# User_Interface.net
KiCad netlist of a schematic drawn in Altium Designer
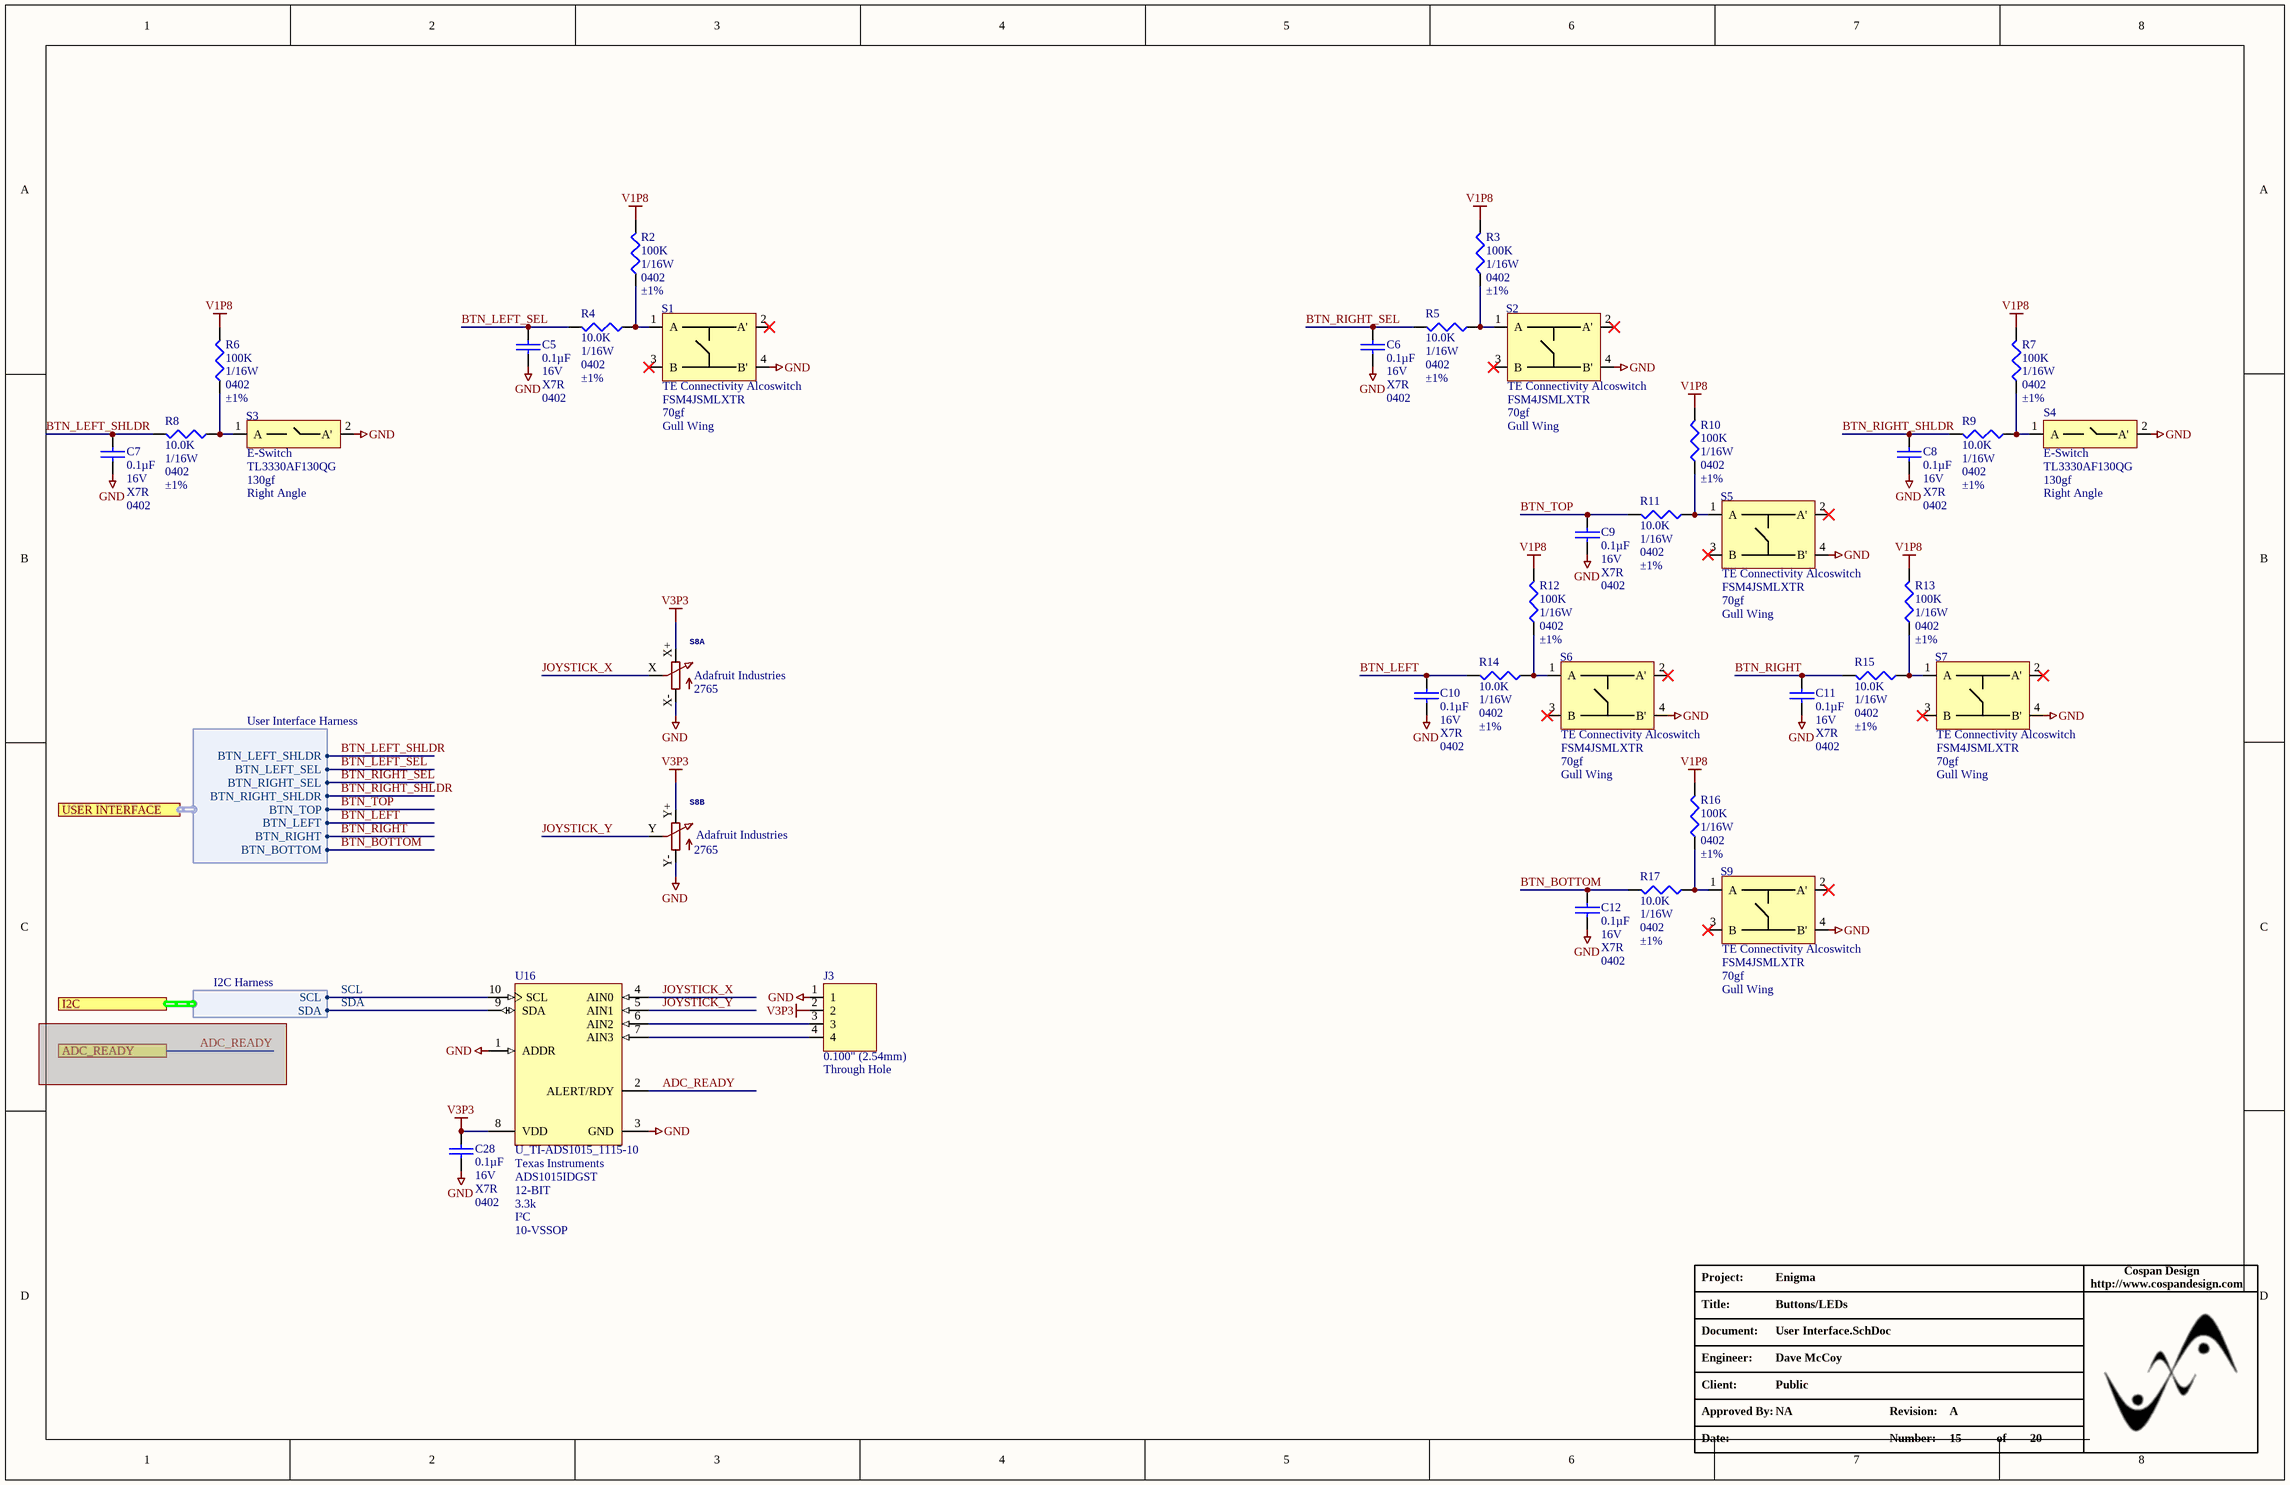
[diagram p0: User Interface.SchDoc]

(export (version "E")
  (design (tool "Eeschema 10.0.6"))
  (components
    (comp (ref "C5")
      (value "0.1uF")
      (footprint "C_0402")
      (description "CAP CER .10UF 16V X7R 0402")
      (fields
        (field (name "MANUFACTURER") "Murata Electronics North America")
        (field (name "MANUFACTURER PART NUMBER") "GRM155R71C104KA88J")
        (field (name "CAPACITANCE") "0.1µF")
        (field (name "VOLTAGE - RATED") "16V")
        (field (name "TEMPERATURE COEFFICIENT") "X7R")
        (field (name "PACKAGE / CASE") "0402")
      )
      (libsource (lib "Main LibraryX") (part "C_0402_0.1UF_16V"))
    )
    (comp (ref "C6")
      (value "0.1uF")
      (footprint "C_0402")
      (description "CAP CER .10UF 16V X7R 0402")
      (fields
        (field (name "MANUFACTURER") "Murata Electronics North America")
        (field (name "MANUFACTURER PART NUMBER") "GRM155R71C104KA88J")
        (field (name "CAPACITANCE") "0.1µF")
        (field (name "VOLTAGE - RATED") "16V")
        (field (name "TEMPERATURE COEFFICIENT") "X7R")
        (field (name "PACKAGE / CASE") "0402")
      )
      (libsource (lib "Main LibraryX") (part "C_0402_0.1UF_16V"))
    )
    (comp (ref "C7")
      (value "0.1uF")
      (footprint "C_0402")
      (description "CAP CER .10UF 16V X7R 0402")
      (fields
        (field (name "MANUFACTURER") "Murata Electronics North America")
        (field (name "MANUFACTURER PART NUMBER") "GRM155R71C104KA88J")
        (field (name "CAPACITANCE") "0.1µF")
        (field (name "VOLTAGE - RATED") "16V")
        (field (name "TEMPERATURE COEFFICIENT") "X7R")
        (field (name "PACKAGE / CASE") "0402")
      )
      (libsource (lib "Main LibraryX") (part "C_0402_0.1UF_16V"))
    )
    (comp (ref "C8")
      (value "0.1uF")
      (footprint "C_0402")
      (description "CAP CER .10UF 16V X7R 0402")
      (fields
        (field (name "MANUFACTURER") "Murata Electronics North America")
        (field (name "MANUFACTURER PART NUMBER") "GRM155R71C104KA88J")
        (field (name "CAPACITANCE") "0.1µF")
        (field (name "VOLTAGE - RATED") "16V")
        (field (name "TEMPERATURE COEFFICIENT") "X7R")
        (field (name "PACKAGE / CASE") "0402")
      )
      (libsource (lib "Main LibraryX") (part "C_0402_0.1UF_16V"))
    )
    (comp (ref "C9")
      (value "0.1uF")
      (footprint "C_0402")
      (description "CAP CER .10UF 16V X7R 0402")
      (fields
        (field (name "MANUFACTURER") "Murata Electronics North America")
        (field (name "MANUFACTURER PART NUMBER") "GRM155R71C104KA88J")
        (field (name "CAPACITANCE") "0.1µF")
        (field (name "VOLTAGE - RATED") "16V")
        (field (name "TEMPERATURE COEFFICIENT") "X7R")
        (field (name "PACKAGE / CASE") "0402")
      )
      (libsource (lib "Main LibraryX") (part "C_0402_0.1UF_16V"))
    )
    (comp (ref "C10")
      (value "0.1uF")
      (footprint "C_0402")
      (description "CAP CER .10UF 16V X7R 0402")
      (fields
        (field (name "MANUFACTURER") "Murata Electronics North America")
        (field (name "MANUFACTURER PART NUMBER") "GRM155R71C104KA88J")
        (field (name "CAPACITANCE") "0.1µF")
        (field (name "VOLTAGE - RATED") "16V")
        (field (name "TEMPERATURE COEFFICIENT") "X7R")
        (field (name "PACKAGE / CASE") "0402")
      )
      (libsource (lib "Main LibraryX") (part "C_0402_0.1UF_16V"))
    )
    (comp (ref "C11")
      (value "0.1uF")
      (footprint "C_0402")
      (description "CAP CER .10UF 16V X7R 0402")
      (fields
        (field (name "MANUFACTURER") "Murata Electronics North America")
        (field (name "MANUFACTURER PART NUMBER") "GRM155R71C104KA88J")
        (field (name "CAPACITANCE") "0.1µF")
        (field (name "VOLTAGE - RATED") "16V")
        (field (name "TEMPERATURE COEFFICIENT") "X7R")
        (field (name "PACKAGE / CASE") "0402")
      )
      (libsource (lib "Main LibraryX") (part "C_0402_0.1UF_16V"))
    )
    (comp (ref "C12")
      (value "0.1uF")
      (footprint "C_0402")
      (description "CAP CER .10UF 16V X7R 0402")
      (fields
        (field (name "MANUFACTURER") "Murata Electronics North America")
        (field (name "MANUFACTURER PART NUMBER") "GRM155R71C104KA88J")
        (field (name "CAPACITANCE") "0.1µF")
        (field (name "VOLTAGE - RATED") "16V")
        (field (name "TEMPERATURE COEFFICIENT") "X7R")
        (field (name "PACKAGE / CASE") "0402")
      )
      (libsource (lib "Main LibraryX") (part "C_0402_0.1UF_16V"))
    )
    (comp (ref "C28")
      (value "0.1uF")
      (footprint "C_0402")
      (description "CAP CER .10UF 16V X7R 0402")
      (fields
        (field (name "MANUFACTURER") "Murata Electronics North America")
        (field (name "MANUFACTURER PART NUMBER") "GRM155R71C104KA88J")
        (field (name "CAPACITANCE") "0.1µF")
        (field (name "VOLTAGE - RATED") "16V")
        (field (name "TEMPERATURE COEFFICIENT") "X7R")
        (field (name "PACKAGE / CASE") "0402")
      )
      (libsource (lib "Main LibraryX") (part "C_0402_0.1UF_16V"))
    )
    (comp (ref "J3")
      (value "J_HDR1X4_THRHOLE_VERT_FEMALE")
      (footprint "HDR_1X4_FEMALE")
      (description "CONN HEADER .100\" 4POS TIN PCB")
      (fields
        (field (name "MANUFACTURER") "Samtec Inc")
        (field (name "MANUFACTURER PART NUMBER") "SSW-116-01-T-S")
        (field (name "PITCH") "0.100\" (2.54mm)")
        (field (name "MOUNTING TYPE") "Through Hole")
      )
      (libsource (lib "Main Library") (part "J_HDR1X4_THRHOLE_VERT_FEMALE"))
    )
    (comp (ref "R2")
      (value "R_0402_100K")
      (footprint "R_0402")
      (description "RES SMD 100K OHM 1% 1/16W 0402")
      (fields
        (field (name "MANUFACTURER") "Yageo")
        (field (name "MANUFACTURER PART NUMBER") "RC0402FR-07100KL")
        (field (name "RESISTANCE IN OHMS") "100K")
        (field (name "POWER (WATTS)") "1/16W")
        (field (name "CASE") "0402")
        (field (name "TOLERANCE") "±1%")
      )
      (libsource (lib "Cospan Design") (part "R_0402_100K"))
    )
    (comp (ref "R3")
      (value "R_0402_100K")
      (footprint "R_0402")
      (description "RES SMD 100K OHM 1% 1/16W 0402")
      (fields
        (field (name "MANUFACTURER") "Yageo")
        (field (name "MANUFACTURER PART NUMBER") "RC0402FR-07100KL")
        (field (name "RESISTANCE IN OHMS") "100K")
        (field (name "POWER (WATTS)") "1/16W")
        (field (name "CASE") "0402")
        (field (name "TOLERANCE") "±1%")
      )
      (libsource (lib "Cospan Design") (part "R_0402_100K"))
    )
    (comp (ref "R4")
      (value "R_0402_10.0K")
      (footprint "R_0402")
      (description "RES 10.0K OHM 1/16W 1% 0402 SMD")
      (fields
        (field (name "MANUFACTURER") "Stackpole Electronics Inc")
        (field (name "MANUFACTURER PART NUMBER") "RMCF0402FT10K0")
        (field (name "RESISTANCE IN OHMS") "10.0K")
        (field (name "POWER (WATTS)") "1/16W")
        (field (name "CASE") "0402")
        (field (name "TOLERANCE") "±1%")
      )
      (libsource (lib "Cospan Design") (part "R_0402_10.0K"))
    )
    (comp (ref "R5")
      (value "R_0402_10.0K")
      (footprint "R_0402")
      (description "RES 10.0K OHM 1/16W 1% 0402 SMD")
      (fields
        (field (name "MANUFACTURER") "Stackpole Electronics Inc")
        (field (name "MANUFACTURER PART NUMBER") "RMCF0402FT10K0")
        (field (name "RESISTANCE IN OHMS") "10.0K")
        (field (name "POWER (WATTS)") "1/16W")
        (field (name "CASE") "0402")
        (field (name "TOLERANCE") "±1%")
      )
      (libsource (lib "Cospan Design") (part "R_0402_10.0K"))
    )
    (comp (ref "R6")
      (value "R_0402_100K")
      (footprint "R_0402")
      (description "RES SMD 100K OHM 1% 1/16W 0402")
      (fields
        (field (name "MANUFACTURER") "Yageo")
        (field (name "MANUFACTURER PART NUMBER") "RC0402FR-07100KL")
        (field (name "RESISTANCE IN OHMS") "100K")
        (field (name "POWER (WATTS)") "1/16W")
        (field (name "CASE") "0402")
        (field (name "TOLERANCE") "±1%")
      )
      (libsource (lib "Cospan Design") (part "R_0402_100K"))
    )
    (comp (ref "R7")
      (value "R_0402_100K")
      (footprint "R_0402")
      (description "RES SMD 100K OHM 1% 1/16W 0402")
      (fields
        (field (name "MANUFACTURER") "Yageo")
        (field (name "MANUFACTURER PART NUMBER") "RC0402FR-07100KL")
        (field (name "RESISTANCE IN OHMS") "100K")
        (field (name "POWER (WATTS)") "1/16W")
        (field (name "CASE") "0402")
        (field (name "TOLERANCE") "±1%")
      )
      (libsource (lib "Cospan Design") (part "R_0402_100K"))
    )
    (comp (ref "R8")
      (value "R_0402_10.0K")
      (footprint "R_0402")
      (description "RES 10.0K OHM 1/16W 1% 0402 SMD")
      (fields
        (field (name "MANUFACTURER") "Stackpole Electronics Inc")
        (field (name "MANUFACTURER PART NUMBER") "RMCF0402FT10K0")
        (field (name "RESISTANCE IN OHMS") "10.0K")
        (field (name "POWER (WATTS)") "1/16W")
        (field (name "CASE") "0402")
        (field (name "TOLERANCE") "±1%")
      )
      (libsource (lib "Cospan Design") (part "R_0402_10.0K"))
    )
    (comp (ref "R9")
      (value "R_0402_10.0K")
      (footprint "R_0402")
      (description "RES 10.0K OHM 1/16W 1% 0402 SMD")
      (fields
        (field (name "MANUFACTURER") "Stackpole Electronics Inc")
        (field (name "MANUFACTURER PART NUMBER") "RMCF0402FT10K0")
        (field (name "RESISTANCE IN OHMS") "10.0K")
        (field (name "POWER (WATTS)") "1/16W")
        (field (name "CASE") "0402")
        (field (name "TOLERANCE") "±1%")
      )
      (libsource (lib "Cospan Design") (part "R_0402_10.0K"))
    )
    (comp (ref "R10")
      (value "R_0402_100K")
      (footprint "R_0402")
      (description "RES SMD 100K OHM 1% 1/16W 0402")
      (fields
        (field (name "MANUFACTURER") "Yageo")
        (field (name "MANUFACTURER PART NUMBER") "RC0402FR-07100KL")
        (field (name "RESISTANCE IN OHMS") "100K")
        (field (name "POWER (WATTS)") "1/16W")
        (field (name "CASE") "0402")
        (field (name "TOLERANCE") "±1%")
      )
      (libsource (lib "Cospan Design") (part "R_0402_100K"))
    )
    (comp (ref "R11")
      (value "R_0402_10.0K")
      (footprint "R_0402")
      (description "RES 10.0K OHM 1/16W 1% 0402 SMD")
      (fields
        (field (name "MANUFACTURER") "Stackpole Electronics Inc")
        (field (name "MANUFACTURER PART NUMBER") "RMCF0402FT10K0")
        (field (name "RESISTANCE IN OHMS") "10.0K")
        (field (name "POWER (WATTS)") "1/16W")
        (field (name "CASE") "0402")
        (field (name "TOLERANCE") "±1%")
      )
      (libsource (lib "Cospan Design") (part "R_0402_10.0K"))
    )
    (comp (ref "R12")
      (value "R_0402_100K")
      (footprint "R_0402")
      (description "RES SMD 100K OHM 1% 1/16W 0402")
      (fields
        (field (name "MANUFACTURER") "Yageo")
        (field (name "MANUFACTURER PART NUMBER") "RC0402FR-07100KL")
        (field (name "RESISTANCE IN OHMS") "100K")
        (field (name "POWER (WATTS)") "1/16W")
        (field (name "CASE") "0402")
        (field (name "TOLERANCE") "±1%")
      )
      (libsource (lib "Cospan Design") (part "R_0402_100K"))
    )
    (comp (ref "R13")
      (value "R_0402_100K")
      (footprint "R_0402")
      (description "RES SMD 100K OHM 1% 1/16W 0402")
      (fields
        (field (name "MANUFACTURER") "Yageo")
        (field (name "MANUFACTURER PART NUMBER") "RC0402FR-07100KL")
        (field (name "RESISTANCE IN OHMS") "100K")
        (field (name "POWER (WATTS)") "1/16W")
        (field (name "CASE") "0402")
        (field (name "TOLERANCE") "±1%")
      )
      (libsource (lib "Cospan Design") (part "R_0402_100K"))
    )
    (comp (ref "R14")
      (value "R_0402_10.0K")
      (footprint "R_0402")
      (description "RES 10.0K OHM 1/16W 1% 0402 SMD")
      (fields
        (field (name "MANUFACTURER") "Stackpole Electronics Inc")
        (field (name "MANUFACTURER PART NUMBER") "RMCF0402FT10K0")
        (field (name "RESISTANCE IN OHMS") "10.0K")
        (field (name "POWER (WATTS)") "1/16W")
        (field (name "CASE") "0402")
        (field (name "TOLERANCE") "±1%")
      )
      (libsource (lib "Cospan Design") (part "R_0402_10.0K"))
    )
    (comp (ref "R15")
      (value "R_0402_10.0K")
      (footprint "R_0402")
      (description "RES 10.0K OHM 1/16W 1% 0402 SMD")
      (fields
        (field (name "MANUFACTURER") "Stackpole Electronics Inc")
        (field (name "MANUFACTURER PART NUMBER") "RMCF0402FT10K0")
        (field (name "RESISTANCE IN OHMS") "10.0K")
        (field (name "POWER (WATTS)") "1/16W")
        (field (name "CASE") "0402")
        (field (name "TOLERANCE") "±1%")
      )
      (libsource (lib "Cospan Design") (part "R_0402_10.0K"))
    )
    (comp (ref "R16")
      (value "R_0402_100K")
      (footprint "R_0402")
      (description "RES SMD 100K OHM 1% 1/16W 0402")
      (fields
        (field (name "MANUFACTURER") "Yageo")
        (field (name "MANUFACTURER PART NUMBER") "RC0402FR-07100KL")
        (field (name "RESISTANCE IN OHMS") "100K")
        (field (name "POWER (WATTS)") "1/16W")
        (field (name "CASE") "0402")
        (field (name "TOLERANCE") "±1%")
      )
      (libsource (lib "Cospan Design") (part "R_0402_100K"))
    )
    (comp (ref "R17")
      (value "R_0402_10.0K")
      (footprint "R_0402")
      (description "RES 10.0K OHM 1/16W 1% 0402 SMD")
      (fields
        (field (name "MANUFACTURER") "Stackpole Electronics Inc")
        (field (name "MANUFACTURER PART NUMBER") "RMCF0402FT10K0")
        (field (name "RESISTANCE IN OHMS") "10.0K")
        (field (name "POWER (WATTS)") "1/16W")
        (field (name "CASE") "0402")
        (field (name "TOLERANCE") "±1%")
      )
      (libsource (lib "Cospan Design") (part "R_0402_10.0K"))
    )
    (comp (ref "S1")
      (value "S_TACTILE_1571563_2_BUTTON")
      (footprint "TACTILE_1571563_2")
      (description "SWITCH TACTILE SPST-NO 0.05A 24V")
      (fields
        (field (name "MANUFACTURER") "TE Connectivity Alcoswitch")
        (field (name "MANUFACTURER PART NUMBER") "FSM4JSMLXTR")
        (field (name "OPERATING FORCE") "70gf")
        (field (name "TERMINATION") "Gull Wing")
      )
      (libsource (lib "Cospan Design") (part "S_TACTILE_1571563_2_BUTTON"))
    )
    (comp (ref "S2")
      (value "S_TACTILE_1571563_2_BUTTON")
      (footprint "TACTILE_1571563_2")
      (description "SWITCH TACTILE SPST-NO 0.05A 24V")
      (fields
        (field (name "MANUFACTURER") "TE Connectivity Alcoswitch")
        (field (name "MANUFACTURER PART NUMBER") "FSM4JSMLXTR")
        (field (name "OPERATING FORCE") "70gf")
        (field (name "TERMINATION") "Gull Wing")
      )
      (libsource (lib "Cospan Design") (part "S_TACTILE_1571563_2_BUTTON"))
    )
    (comp (ref "S3")
      (value "S_TACTILE_ RA_TL3330AF130QG_BUTTON")
      (footprint "TL3330AF130QG")
      (description "SWITCH TACTILE SPST-NO 0.05A 12V")
      (fields
        (field (name "MANUFACTURER") "E-Switch")
        (field (name "MANUFACTURER PART NUMBER") "TL3330AF130QG")
        (field (name "OPERATING FORCE") "130gf")
        (field (name "ORIENTATION") "Right Angle")
      )
      (libsource (lib "Cospan Design") (part "S_TACTILE_ RA_TL3330AF130QG_BUTTON"))
    )
    (comp (ref "S4")
      (value "S_TACTILE_ RA_TL3330AF130QG_BUTTON")
      (footprint "TL3330AF130QG")
      (description "SWITCH TACTILE SPST-NO 0.05A 12V")
      (fields
        (field (name "MANUFACTURER") "E-Switch")
        (field (name "MANUFACTURER PART NUMBER") "TL3330AF130QG")
        (field (name "OPERATING FORCE") "130gf")
        (field (name "ORIENTATION") "Right Angle")
      )
      (libsource (lib "Cospan Design") (part "S_TACTILE_ RA_TL3330AF130QG_BUTTON"))
    )
    (comp (ref "S5")
      (value "S_TACTILE_1571563_2_BUTTON")
      (footprint "TACTILE_1571563_2")
      (description "SWITCH TACTILE SPST-NO 0.05A 24V")
      (fields
        (field (name "MANUFACTURER") "TE Connectivity Alcoswitch")
        (field (name "MANUFACTURER PART NUMBER") "FSM4JSMLXTR")
        (field (name "OPERATING FORCE") "70gf")
        (field (name "TERMINATION") "Gull Wing")
      )
      (libsource (lib "Cospan Design") (part "S_TACTILE_1571563_2_BUTTON"))
    )
    (comp (ref "S6")
      (value "S_TACTILE_1571563_2_BUTTON")
      (footprint "TACTILE_1571563_2")
      (description "SWITCH TACTILE SPST-NO 0.05A 24V")
      (fields
        (field (name "MANUFACTURER") "TE Connectivity Alcoswitch")
        (field (name "MANUFACTURER PART NUMBER") "FSM4JSMLXTR")
        (field (name "OPERATING FORCE") "70gf")
        (field (name "TERMINATION") "Gull Wing")
      )
      (libsource (lib "Cospan Design") (part "S_TACTILE_1571563_2_BUTTON"))
    )
    (comp (ref "S7")
      (value "S_TACTILE_1571563_2_BUTTON")
      (footprint "TACTILE_1571563_2")
      (description "SWITCH TACTILE SPST-NO 0.05A 24V")
      (fields
        (field (name "MANUFACTURER") "TE Connectivity Alcoswitch")
        (field (name "MANUFACTURER PART NUMBER") "FSM4JSMLXTR")
        (field (name "OPERATING FORCE") "70gf")
        (field (name "TERMINATION") "Gull Wing")
      )
      (libsource (lib "Cospan Design") (part "S_TACTILE_1571563_2_BUTTON"))
    )
    (comp (ref "S8")
      (value "S_JOYSTICK_ANALOG_XY")
      (footprint "JOYSTICK_ANALOG_MINITHM")
      (fields
        (field (name "MANUFACTURER") "Adafruit Industries")
        (field (name "MANUFACTURER PART NUMBER") "2765")
      )
      (libsource (lib "Cospan Design") (part "S_JOYSTICK_ANALOG_XY"))
    )
    (comp (ref "S9")
      (value "S_TACTILE_1571563_2_BUTTON")
      (footprint "TACTILE_1571563_2")
      (description "SWITCH TACTILE SPST-NO 0.05A 24V")
      (fields
        (field (name "MANUFACTURER") "TE Connectivity Alcoswitch")
        (field (name "MANUFACTURER PART NUMBER") "FSM4JSMLXTR")
        (field (name "OPERATING FORCE") "70gf")
        (field (name "TERMINATION") "Gull Wing")
      )
      (libsource (lib "Cospan Design") (part "S_TACTILE_1571563_2_BUTTON"))
    )
    (comp (ref "U16")
      (value "U_TI-ADS1015_1115-10")
      (footprint "TI-DGS10_L")
      (description "IC ADC 12BIT I2C W/REF 10-MSOP")
      (fields
        (field (name "MANUFACTURER") "Texas Instruments")
        (field (name "MANUFACTURER PART NUMBER") "ADS1015IDGST")
        (field (name "NUMBER OF BITS") "12-BIT")
        (field (name "SAMPLING RATE (PER SECOND)") "3.3k")
        (field (name "DATA INTERFACE") "I²C")
        (field (name "SUPPLIER DEVICE PACKAGE") "10-VSSOP")
      )
      (libsource (lib "Main Library") (part "U_TI-ADS1015_1115-10"))
    )
  )
  (nets
    (net (code "5") (name "/ADC_READY") (class "Default")
      (node (ref "U16") (pin "2") (pinfunction "ALERT/RDY_2") (pintype "open_collector"))
    )
    (net (code "6") (name "/BTN_BOTTOM") (class "Default")
      (node (ref "C12") (pin "2") (pinfunction "2_2") (pintype "passive"))
      (node (ref "R17") (pin "1") (pinfunction "1_1") (pintype "passive"))
    )
    (net (code "7") (name "/BTN_LEFT") (class "Default")
      (node (ref "C10") (pin "2") (pinfunction "2_2") (pintype "passive"))
      (node (ref "R14") (pin "1") (pinfunction "1_1") (pintype "passive"))
    )
    (net (code "8") (name "/BTN_LEFT_SEL") (class "Default")
      (node (ref "C5") (pin "2") (pinfunction "2_2") (pintype "passive"))
      (node (ref "R4") (pin "1") (pinfunction "1_1") (pintype "passive"))
    )
    (net (code "9") (name "/BTN_LEFT_SHLDR") (class "Default")
      (node (ref "C7") (pin "2") (pinfunction "2_2") (pintype "passive"))
      (node (ref "R8") (pin "1") (pinfunction "1_1") (pintype "passive"))
    )
    (net (code "10") (name "/BTN_RIGHT") (class "Default")
      (node (ref "C11") (pin "2") (pinfunction "2_2") (pintype "passive"))
      (node (ref "R15") (pin "1") (pinfunction "1_1") (pintype "passive"))
    )
    (net (code "11") (name "/BTN_RIGHT_SEL") (class "Default")
      (node (ref "C6") (pin "2") (pinfunction "2_2") (pintype "passive"))
      (node (ref "R5") (pin "1") (pinfunction "1_1") (pintype "passive"))
    )
    (net (code "12") (name "/BTN_RIGHT_SHLDR") (class "Default")
      (node (ref "C8") (pin "2") (pinfunction "2_2") (pintype "passive"))
      (node (ref "R9") (pin "1") (pinfunction "1_1") (pintype "passive"))
    )
    (net (code "13") (name "/BTN_TOP") (class "Default")
      (node (ref "C9") (pin "2") (pinfunction "2_2") (pintype "passive"))
      (node (ref "R11") (pin "1") (pinfunction "1_1") (pintype "passive"))
    )
    (net (code "14") (name "/JOYSTICK_X") (class "Default")
      (node (ref "S8") (pin "X") (pinfunction "S_X") (pintype "passive"))
      (node (ref "U16") (pin "4") (pinfunction "AIN0_4") (pintype "input"))
    )
    (net (code "15") (name "/JOYSTICK_Y") (class "Default")
      (node (ref "S8") (pin "Y") (pinfunction "S_Y") (pintype "passive"))
      (node (ref "U16") (pin "5") (pinfunction "AIN1_5") (pintype "input"))
    )
    (net (code "16") (name "/SCL") (class "Default")
      (node (ref "U16") (pin "10") (pinfunction "SCL_10") (pintype "input"))
    )
    (net (code "17") (name "/SDA") (class "Default")
      (node (ref "U16") (pin "9") (pinfunction "SDA_9") (pintype "bidirectional"))
    )
    (net (code "20") (name "GND") (class "Default")
      (node (ref "C10") (pin "1") (pinfunction "1_1") (pintype "passive"))
      (node (ref "C11") (pin "1") (pinfunction "1_1") (pintype "passive"))
      (node (ref "C12") (pin "1") (pinfunction "1_1") (pintype "passive"))
      (node (ref "C28") (pin "1") (pinfunction "1_1") (pintype "passive"))
      (node (ref "C5") (pin "1") (pinfunction "1_1") (pintype "passive"))
      (node (ref "C6") (pin "1") (pinfunction "1_1") (pintype "passive"))
      (node (ref "C7") (pin "1") (pinfunction "1_1") (pintype "passive"))
      (node (ref "C8") (pin "1") (pinfunction "1_1") (pintype "passive"))
      (node (ref "C9") (pin "1") (pinfunction "1_1") (pintype "passive"))
      (node (ref "J3") (pin "1") (pinfunction "1_1") (pintype "passive"))
      (node (ref "S1") (pin "4") (pinfunction "B'_4") (pintype "passive"))
      (node (ref "S2") (pin "4") (pinfunction "B'_4") (pintype "passive"))
      (node (ref "S3") (pin "2") (pinfunction "A'_2") (pintype "passive"))
      (node (ref "S4") (pin "2") (pinfunction "A'_2") (pintype "passive"))
      (node (ref "S5") (pin "4") (pinfunction "B'_4") (pintype "passive"))
      (node (ref "S6") (pin "4") (pinfunction "B'_4") (pintype "passive"))
      (node (ref "S7") (pin "4") (pinfunction "B'_4") (pintype "passive"))
      (node (ref "S8") (pin "X-") (pinfunction "A_X-") (pintype "passive"))
      (node (ref "S8") (pin "Y-") (pinfunction "A_Y-") (pintype "passive"))
      (node (ref "S9") (pin "4") (pinfunction "B'_4") (pintype "passive"))
      (node (ref "U16") (pin "1") (pinfunction "ADDR_1") (pintype "input"))
      (node (ref "U16") (pin "3") (pinfunction "GND_3") (pintype "power_in"))
    )
    (net (code "21") (name "Net-(S1-A)") (class "Default")
      (node (ref "R2") (pin "2") (pinfunction "2_2") (pintype "passive"))
      (node (ref "R4") (pin "2") (pinfunction "2_2") (pintype "passive"))
      (node (ref "S1") (pin "1") (pinfunction "A_1") (pintype "passive"))
    )
    (net (code "22") (name "Net-(S2-A)") (class "Default")
      (node (ref "R3") (pin "2") (pinfunction "2_2") (pintype "passive"))
      (node (ref "R5") (pin "2") (pinfunction "2_2") (pintype "passive"))
      (node (ref "S2") (pin "1") (pinfunction "A_1") (pintype "passive"))
    )
    (net (code "23") (name "Net-(S3-A)") (class "Default")
      (node (ref "R6") (pin "2") (pinfunction "2_2") (pintype "passive"))
      (node (ref "R8") (pin "2") (pinfunction "2_2") (pintype "passive"))
      (node (ref "S3") (pin "1") (pinfunction "A_1") (pintype "passive"))
    )
    (net (code "24") (name "Net-(S4-A)") (class "Default")
      (node (ref "R7") (pin "2") (pinfunction "2_2") (pintype "passive"))
      (node (ref "R9") (pin "2") (pinfunction "2_2") (pintype "passive"))
      (node (ref "S4") (pin "1") (pinfunction "A_1") (pintype "passive"))
    )
    (net (code "25") (name "Net-(S5-A)") (class "Default")
      (node (ref "R10") (pin "2") (pinfunction "2_2") (pintype "passive"))
      (node (ref "R11") (pin "2") (pinfunction "2_2") (pintype "passive"))
      (node (ref "S5") (pin "1") (pinfunction "A_1") (pintype "passive"))
    )
    (net (code "26") (name "Net-(S6-A)") (class "Default")
      (node (ref "R12") (pin "2") (pinfunction "2_2") (pintype "passive"))
      (node (ref "R14") (pin "2") (pinfunction "2_2") (pintype "passive"))
      (node (ref "S6") (pin "1") (pinfunction "A_1") (pintype "passive"))
    )
    (net (code "27") (name "Net-(S7-A)") (class "Default")
      (node (ref "R13") (pin "2") (pinfunction "2_2") (pintype "passive"))
      (node (ref "R15") (pin "2") (pinfunction "2_2") (pintype "passive"))
      (node (ref "S7") (pin "1") (pinfunction "A_1") (pintype "passive"))
    )
    (net (code "28") (name "Net-(S9-A)") (class "Default")
      (node (ref "R16") (pin "2") (pinfunction "2_2") (pintype "passive"))
      (node (ref "R17") (pin "2") (pinfunction "2_2") (pintype "passive"))
      (node (ref "S9") (pin "1") (pinfunction "A_1") (pintype "passive"))
    )
    (net (code "29") (name "Net-(U16-AIN2)") (class "Default")
      (node (ref "J3") (pin "3") (pinfunction "3_3") (pintype "passive"))
      (node (ref "U16") (pin "6") (pinfunction "AIN2_6") (pintype "input"))
    )
    (net (code "30") (name "Net-(U16-AIN3)") (class "Default")
      (node (ref "J3") (pin "4") (pinfunction "4_4") (pintype "passive"))
      (node (ref "U16") (pin "7") (pinfunction "AIN3_7") (pintype "input"))
    )
    (net (code "31") (name "V1P8") (class "Default")
      (node (ref "R10") (pin "1") (pinfunction "1_1") (pintype "passive"))
      (node (ref "R12") (pin "1") (pinfunction "1_1") (pintype "passive"))
      (node (ref "R13") (pin "1") (pinfunction "1_1") (pintype "passive"))
      (node (ref "R16") (pin "1") (pinfunction "1_1") (pintype "passive"))
      (node (ref "R2") (pin "1") (pinfunction "1_1") (pintype "passive"))
      (node (ref "R3") (pin "1") (pinfunction "1_1") (pintype "passive"))
      (node (ref "R6") (pin "1") (pinfunction "1_1") (pintype "passive"))
      (node (ref "R7") (pin "1") (pinfunction "1_1") (pintype "passive"))
    )
    (net (code "32") (name "V3P3") (class "Default")
      (node (ref "C28") (pin "2") (pinfunction "2_2") (pintype "passive"))
      (node (ref "J3") (pin "2") (pinfunction "2_2") (pintype "passive"))
      (node (ref "S8") (pin "X+") (pinfunction "E_X+") (pintype "passive"))
      (node (ref "S8") (pin "Y+") (pinfunction "E_Y+") (pintype "passive"))
      (node (ref "U16") (pin "8") (pinfunction "VDD_8") (pintype "power_in"))
    )
    (net (code "33") (name "unconnected-(S1-A'-Pad2)") (class "Default")
      (node (ref "S1") (pin "2") (pinfunction "A'_2") (pintype "passive+no_connect"))
    )
    (net (code "34") (name "unconnected-(S1-B-Pad3)") (class "Default")
      (node (ref "S1") (pin "3") (pinfunction "B_3") (pintype "passive+no_connect"))
    )
    (net (code "35") (name "unconnected-(S2-A'-Pad2)") (class "Default")
      (node (ref "S2") (pin "2") (pinfunction "A'_2") (pintype "passive+no_connect"))
    )
    (net (code "36") (name "unconnected-(S2-B-Pad3)") (class "Default")
      (node (ref "S2") (pin "3") (pinfunction "B_3") (pintype "passive+no_connect"))
    )
    (net (code "37") (name "unconnected-(S5-A'-Pad2)") (class "Default")
      (node (ref "S5") (pin "2") (pinfunction "A'_2") (pintype "passive+no_connect"))
    )
    (net (code "38") (name "unconnected-(S5-B-Pad3)") (class "Default")
      (node (ref "S5") (pin "3") (pinfunction "B_3") (pintype "passive+no_connect"))
    )
    (net (code "39") (name "unconnected-(S6-A'-Pad2)") (class "Default")
      (node (ref "S6") (pin "2") (pinfunction "A'_2") (pintype "passive+no_connect"))
    )
    (net (code "40") (name "unconnected-(S6-B-Pad3)") (class "Default")
      (node (ref "S6") (pin "3") (pinfunction "B_3") (pintype "passive+no_connect"))
    )
    (net (code "41") (name "unconnected-(S7-A'-Pad2)") (class "Default")
      (node (ref "S7") (pin "2") (pinfunction "A'_2") (pintype "passive+no_connect"))
    )
    (net (code "42") (name "unconnected-(S7-B-Pad3)") (class "Default")
      (node (ref "S7") (pin "3") (pinfunction "B_3") (pintype "passive+no_connect"))
    )
    (net (code "43") (name "unconnected-(S9-A'-Pad2)") (class "Default")
      (node (ref "S9") (pin "2") (pinfunction "A'_2") (pintype "passive+no_connect"))
    )
    (net (code "44") (name "unconnected-(S9-B-Pad3)") (class "Default")
      (node (ref "S9") (pin "3") (pinfunction "B_3") (pintype "passive+no_connect"))
    )
  )
)
